# atsams70n-switch.net
KiCad netlist of a schematic drawn in EAGLE
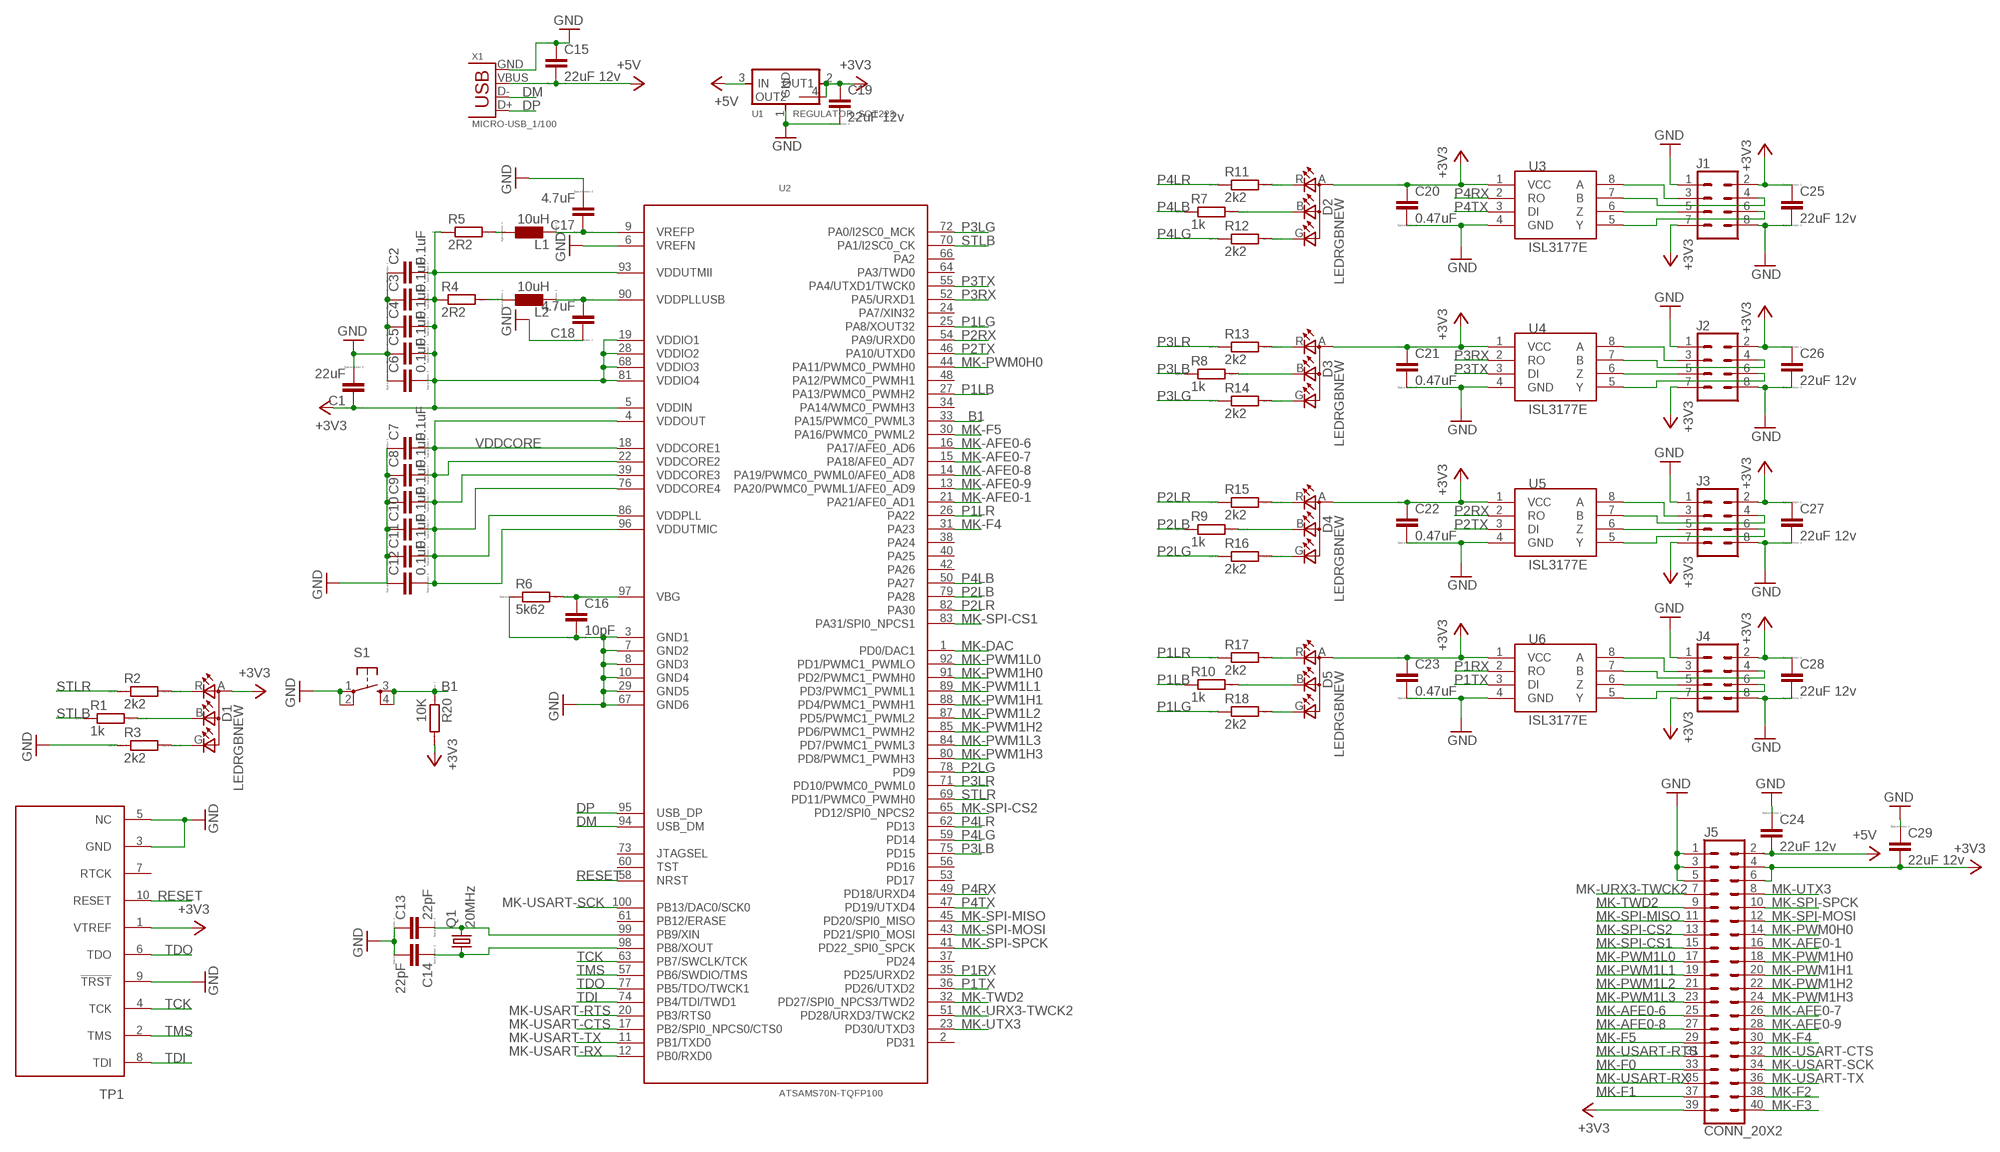
[diagram p0: schematic, sheet 1]

(export (version "E")
  (design (tool "Eeschema 10.0.6"))
  (components
    (comp (ref "C1")
      (value "22uF")
      (footprint "eagle-import:C0805")
      (libsource (lib "eagle-import") (part "C"))
    )
    (comp (ref "C2")
      (value "0.1uF")
      (footprint "eagle-import:C0603")
      (libsource (lib "eagle-import") (part "CC0603"))
    )
    (comp (ref "C3")
      (value "0.1uF")
      (footprint "eagle-import:C0603")
      (libsource (lib "eagle-import") (part "CC0603"))
    )
    (comp (ref "C4")
      (value "0.1uF")
      (footprint "eagle-import:C0603")
      (libsource (lib "eagle-import") (part "CC0603"))
    )
    (comp (ref "C5")
      (value "0.1uF")
      (footprint "eagle-import:C0603")
      (libsource (lib "eagle-import") (part "CC0603"))
    )
    (comp (ref "C6")
      (value "0.1uF")
      (footprint "eagle-import:C0603")
      (libsource (lib "eagle-import") (part "CC0603"))
    )
    (comp (ref "C7")
      (value "0.1uF")
      (footprint "eagle-import:C0603")
      (libsource (lib "eagle-import") (part "CC0603"))
    )
    (comp (ref "C8")
      (value "0.1uF")
      (footprint "eagle-import:C0603")
      (libsource (lib "eagle-import") (part "CC0603"))
    )
    (comp (ref "C9")
      (value "0.1uF")
      (footprint "eagle-import:C0603")
      (libsource (lib "eagle-import") (part "CC0603"))
    )
    (comp (ref "C10")
      (value "0.1uF")
      (footprint "eagle-import:C0603")
      (libsource (lib "eagle-import") (part "CC0603"))
    )
    (comp (ref "C11")
      (value "0.1uF")
      (footprint "eagle-import:C0603")
      (libsource (lib "eagle-import") (part "CC0603"))
    )
    (comp (ref "C12")
      (value "0.1uF")
      (footprint "eagle-import:C0603")
      (libsource (lib "eagle-import") (part "CC0603"))
    )
    (comp (ref "C13")
      (value "22pF")
      (footprint "eagle-import:C0603")
      (libsource (lib "eagle-import") (part "CC0603"))
    )
    (comp (ref "C14")
      (value "22pF")
      (footprint "eagle-import:C0603")
      (libsource (lib "eagle-import") (part "CC0603"))
    )
    (comp (ref "C15")
      (value "22uF 12v")
      (footprint "eagle-import:C0805")
      (libsource (lib "eagle-import") (part "C"))
    )
    (comp (ref "C16")
      (value "10pF")
      (footprint "eagle-import:C0805")
      (libsource (lib "eagle-import") (part "C"))
    )
    (comp (ref "C17")
      (value "4.7uF")
      (footprint "eagle-import:C0805")
      (libsource (lib "eagle-import") (part "C"))
    )
    (comp (ref "C18")
      (value "4.7uF")
      (footprint "eagle-import:C0805")
      (libsource (lib "eagle-import") (part "C"))
    )
    (comp (ref "C19")
      (value "22uF 12v")
      (footprint "eagle-import:C0805")
      (libsource (lib "eagle-import") (part "C"))
    )
    (comp (ref "C20")
      (value "0.47uF")
      (footprint "eagle-import:C0805")
      (libsource (lib "eagle-import") (part "C"))
    )
    (comp (ref "C21")
      (value "0.47uF")
      (footprint "eagle-import:C0805")
      (libsource (lib "eagle-import") (part "C"))
    )
    (comp (ref "C22")
      (value "0.47uF")
      (footprint "eagle-import:C0805")
      (libsource (lib "eagle-import") (part "C"))
    )
    (comp (ref "C23")
      (value "0.47uF")
      (footprint "eagle-import:C0805")
      (libsource (lib "eagle-import") (part "C"))
    )
    (comp (ref "C24")
      (value "22uF 12v")
      (footprint "eagle-import:C0805")
      (libsource (lib "eagle-import") (part "C"))
    )
    (comp (ref "C25")
      (value "22uF 12v")
      (footprint "eagle-import:C0805")
      (libsource (lib "eagle-import") (part "C"))
    )
    (comp (ref "C26")
      (value "22uF 12v")
      (footprint "eagle-import:C0805")
      (libsource (lib "eagle-import") (part "C"))
    )
    (comp (ref "C27")
      (value "22uF 12v")
      (footprint "eagle-import:C0805")
      (libsource (lib "eagle-import") (part "C"))
    )
    (comp (ref "C28")
      (value "22uF 12v")
      (footprint "eagle-import:C0805")
      (libsource (lib "eagle-import") (part "C"))
    )
    (comp (ref "C29")
      (value "22uF 12v")
      (footprint "eagle-import:C0805")
      (libsource (lib "eagle-import") (part "C"))
    )
    (comp (ref "D1")
      (value "LEDRGBNEW")
      (footprint "eagle-import:P-LCC-4")
      (libsource (lib "eagle-import") (part "LEDRGBNEW"))
    )
    (comp (ref "D2")
      (value "LEDRGBNEW")
      (footprint "eagle-import:P-LCC-4")
      (libsource (lib "eagle-import") (part "LEDRGBNEW"))
    )
    (comp (ref "D3")
      (value "LEDRGBNEW")
      (footprint "eagle-import:P-LCC-4")
      (libsource (lib "eagle-import") (part "LEDRGBNEW"))
    )
    (comp (ref "D4")
      (value "LEDRGBNEW")
      (footprint "eagle-import:P-LCC-4")
      (libsource (lib "eagle-import") (part "LEDRGBNEW"))
    )
    (comp (ref "D5")
      (value "LEDRGBNEW")
      (footprint "eagle-import:P-LCC-4")
      (libsource (lib "eagle-import") (part "LEDRGBNEW"))
    )
    (comp (ref "J1")
      (value "CONN_04X2SHROUDED")
      (footprint "eagle-import:2X4-SHROUDED")
      (libsource (lib "eagle-import") (part "CONN_04X2SHROUDED"))
    )
    (comp (ref "J2")
      (value "CONN_04X2SHROUDED")
      (footprint "eagle-import:2X4-SHROUDED")
      (libsource (lib "eagle-import") (part "CONN_04X2SHROUDED"))
    )
    (comp (ref "J3")
      (value "CONN_04X2SHROUDED")
      (footprint "eagle-import:2X4-SHROUDED")
      (libsource (lib "eagle-import") (part "CONN_04X2SHROUDED"))
    )
    (comp (ref "J4")
      (value "CONN_04X2SHROUDED")
      (footprint "eagle-import:2X4-SHROUDED")
      (libsource (lib "eagle-import") (part "CONN_04X2SHROUDED"))
    )
    (comp (ref "J5")
      (value "CONN_20X2")
      (footprint "eagle-import:2X20")
      (libsource (lib "eagle-import") (part "CONN_20X2"))
    )
    (comp (ref "L1")
      (value "10uH")
      (footprint "eagle-import:L1812")
      (libsource (lib "eagle-import") (part "L"))
    )
    (comp (ref "L2")
      (value "10uH")
      (footprint "eagle-import:L1812")
      (libsource (lib "eagle-import") (part "L"))
    )
    (comp (ref "Q1")
      (value "20MHz")
      (footprint "eagle-import:CTS406")
      (libsource (lib "eagle-import") (part "CRYSTALCTS406"))
    )
    (comp (ref "R1")
      (value "1k")
      (footprint "eagle-import:R0805")
      (libsource (lib "eagle-import") (part "R"))
    )
    (comp (ref "R2")
      (value "2k2")
      (footprint "eagle-import:R0805")
      (libsource (lib "eagle-import") (part "R"))
    )
    (comp (ref "R3")
      (value "2k2")
      (footprint "eagle-import:R0805")
      (libsource (lib "eagle-import") (part "R"))
    )
    (comp (ref "R4")
      (value "2R2")
      (footprint "eagle-import:R0805")
      (libsource (lib "eagle-import") (part "R"))
    )
    (comp (ref "R5")
      (value "2R2")
      (footprint "eagle-import:R0805")
      (libsource (lib "eagle-import") (part "R"))
    )
    (comp (ref "R6")
      (value "5k62")
      (footprint "eagle-import:R0805")
      (libsource (lib "eagle-import") (part "R"))
    )
    (comp (ref "R7")
      (value "1k")
      (footprint "eagle-import:R0805")
      (libsource (lib "eagle-import") (part "R"))
    )
    (comp (ref "R8")
      (value "1k")
      (footprint "eagle-import:R0805")
      (libsource (lib "eagle-import") (part "R"))
    )
    (comp (ref "R9")
      (value "1k")
      (footprint "eagle-import:R0805")
      (libsource (lib "eagle-import") (part "R"))
    )
    (comp (ref "R10")
      (value "1k")
      (footprint "eagle-import:R0805")
      (libsource (lib "eagle-import") (part "R"))
    )
    (comp (ref "R11")
      (value "2k2")
      (footprint "eagle-import:R0805")
      (libsource (lib "eagle-import") (part "R"))
    )
    (comp (ref "R12")
      (value "2k2")
      (footprint "eagle-import:R0805")
      (libsource (lib "eagle-import") (part "R"))
    )
    (comp (ref "R13")
      (value "2k2")
      (footprint "eagle-import:R0805")
      (libsource (lib "eagle-import") (part "R"))
    )
    (comp (ref "R14")
      (value "2k2")
      (footprint "eagle-import:R0805")
      (libsource (lib "eagle-import") (part "R"))
    )
    (comp (ref "R15")
      (value "2k2")
      (footprint "eagle-import:R0805")
      (libsource (lib "eagle-import") (part "R"))
    )
    (comp (ref "R16")
      (value "2k2")
      (footprint "eagle-import:R0805")
      (libsource (lib "eagle-import") (part "R"))
    )
    (comp (ref "R17")
      (value "2k2")
      (footprint "eagle-import:R0805")
      (libsource (lib "eagle-import") (part "R"))
    )
    (comp (ref "R18")
      (value "2k2")
      (footprint "eagle-import:R0805")
      (libsource (lib "eagle-import") (part "R"))
    )
    (comp (ref "R20")
      (value "10K")
      (footprint "eagle-import:R0805")
      (libsource (lib "eagle-import") (part "R"))
    )
    (comp (ref "S1")
      (value "6MM_SWITCH6MM_SWITCH")
      (footprint "eagle-import:6MM_SWITCH")
      (libsource (lib "eagle-import") (part "6MM_SWITCH6MM_SWITCH"))
    )
    (comp (ref "TP1")
      (value "TC2050-MCP-NL")
      (footprint "eagle-import:TC2030-MCP-NL")
      (libsource (lib "eagle-import") (part "TC2050-MCP-NL"))
    )
    (comp (ref "U1")
      (value "REGULATOR_SOT223")
      (footprint "eagle-import:SOT223")
      (libsource (lib "eagle-import") (part "REGULATOR_SOT223"))
    )
    (comp (ref "U2")
      (value "ATSAMS70N-TQFP100")
      (footprint "eagle-import:TQFP100-14X14")
      (libsource (lib "eagle-import") (part "ATSAMS70N-TQFP100"))
    )
    (comp (ref "U3")
      (value "ISL3177E")
      (footprint "eagle-import:MSOP8")
      (libsource (lib "eagle-import") (part "ISL3177E"))
    )
    (comp (ref "U4")
      (value "ISL3177E")
      (footprint "eagle-import:MSOP8")
      (libsource (lib "eagle-import") (part "ISL3177E"))
    )
    (comp (ref "U5")
      (value "ISL3177E")
      (footprint "eagle-import:MSOP8")
      (libsource (lib "eagle-import") (part "ISL3177E"))
    )
    (comp (ref "U6")
      (value "ISL3177E")
      (footprint "eagle-import:MSOP8")
      (libsource (lib "eagle-import") (part "ISL3177E"))
    )
    (comp (ref "X1")
      (value "MICRO-USB_1/100")
      (footprint "eagle-import:DX4R005HJ5_100")
      (libsource (lib "eagle-import") (part "MICRO-USB_1/100"))
    )
  )
  (nets
    (net (code "1") (name "+3V3") (class "Default")
      (node (ref "C1") (pin "1") (pinfunction "1_1") (pintype "passive"))
      (node (ref "C19") (pin "1") (pinfunction "1_1") (pintype "passive"))
      (node (ref "C2") (pin "2") (pinfunction "2_2") (pintype "passive"))
      (node (ref "C20") (pin "1") (pinfunction "1_1") (pintype "passive"))
      (node (ref "C21") (pin "1") (pinfunction "1_1") (pintype "passive"))
      (node (ref "C22") (pin "1") (pinfunction "1_1") (pintype "passive"))
      (node (ref "C23") (pin "1") (pinfunction "1_1") (pintype "passive"))
      (node (ref "C25") (pin "1") (pinfunction "1_1") (pintype "passive"))
      (node (ref "C26") (pin "1") (pinfunction "1_1") (pintype "passive"))
      (node (ref "C27") (pin "1") (pinfunction "1_1") (pintype "passive"))
      (node (ref "C28") (pin "1") (pinfunction "1_1") (pintype "passive"))
      (node (ref "C29") (pin "2") (pinfunction "2_2") (pintype "passive"))
      (node (ref "C3") (pin "2") (pinfunction "2_2") (pintype "passive"))
      (node (ref "C4") (pin "2") (pinfunction "2_2") (pintype "passive"))
      (node (ref "C5") (pin "2") (pinfunction "2_2") (pintype "passive"))
      (node (ref "C6") (pin "2") (pinfunction "2_2") (pintype "passive"))
      (node (ref "D1") (pin "A") (pinfunction "A2_A") (pintype "passive"))
      (node (ref "D2") (pin "A") (pinfunction "A2_A") (pintype "passive"))
      (node (ref "D3") (pin "A") (pinfunction "A2_A") (pintype "passive"))
      (node (ref "D4") (pin "A") (pinfunction "A2_A") (pintype "passive"))
      (node (ref "D5") (pin "A") (pinfunction "A2_A") (pintype "passive"))
      (node (ref "J1") (pin "2") (pinfunction "2_2") (pintype "passive"))
      (node (ref "J1") (pin "7") (pinfunction "7_7") (pintype "passive"))
      (node (ref "J2") (pin "2") (pinfunction "2_2") (pintype "passive"))
      (node (ref "J2") (pin "7") (pinfunction "7_7") (pintype "passive"))
      (node (ref "J3") (pin "2") (pinfunction "2_2") (pintype "passive"))
      (node (ref "J3") (pin "7") (pinfunction "7_7") (pintype "passive"))
      (node (ref "J4") (pin "2") (pinfunction "2_2") (pintype "passive"))
      (node (ref "J4") (pin "7") (pinfunction "7_7") (pintype "passive"))
      (node (ref "J5") (pin "39") (pinfunction "39_39") (pintype "passive"))
      (node (ref "J5") (pin "4") (pinfunction "4_4") (pintype "passive"))
      (node (ref "J5") (pin "6") (pinfunction "6_6") (pintype "passive"))
      (node (ref "R20") (pin "2") (pinfunction "2_2") (pintype "passive"))
      (node (ref "R4") (pin "1") (pinfunction "1_1") (pintype "passive"))
      (node (ref "R5") (pin "1") (pinfunction "1_1") (pintype "passive"))
      (node (ref "TP1") (pin "1") (pinfunction "VTREF_1") (pintype "bidirectional"))
      (node (ref "U1") (pin "2") (pinfunction "OUT1_2") (pintype "bidirectional"))
      (node (ref "U1") (pin "4") (pinfunction "OUT2_4") (pintype "bidirectional"))
      (node (ref "U2") (pin "19") (pinfunction "VDDIO1_19") (pintype "bidirectional"))
      (node (ref "U2") (pin "28") (pinfunction "VDDIO2_28") (pintype "bidirectional"))
      (node (ref "U2") (pin "5") (pinfunction "VDDIN_5") (pintype "bidirectional"))
      (node (ref "U2") (pin "68") (pinfunction "VDDIO3_68") (pintype "bidirectional"))
      (node (ref "U2") (pin "81") (pinfunction "VDDIO4_81") (pintype "bidirectional"))
      (node (ref "U2") (pin "93") (pinfunction "VDDUTMII_93") (pintype "bidirectional"))
      (node (ref "U3") (pin "1") (pinfunction "VCC_1") (pintype "bidirectional"))
      (node (ref "U4") (pin "1") (pinfunction "VCC_1") (pintype "bidirectional"))
      (node (ref "U5") (pin "1") (pinfunction "VCC_1") (pintype "bidirectional"))
      (node (ref "U6") (pin "1") (pinfunction "VCC_1") (pintype "bidirectional"))
    )
    (net (code "2") (name "+5V") (class "Default")
      (node (ref "C15") (pin "2") (pinfunction "2_2") (pintype "passive"))
      (node (ref "C24") (pin "2") (pinfunction "2_2") (pintype "passive"))
      (node (ref "J5") (pin "2") (pinfunction "2_2") (pintype "passive"))
      (node (ref "U1") (pin "3") (pinfunction "IN_3") (pintype "bidirectional"))
      (node (ref "X1") (pin "VBUS") (pinfunction "VBUS_VBUS") (pintype "bidirectional"))
    )
    (net (code "3") (name "/B1") (class "Default")
      (node (ref "R20") (pin "1") (pinfunction "1_1") (pintype "passive"))
      (node (ref "S1") (pin "3") (pinfunction "S_3") (pintype "passive"))
      (node (ref "S1") (pin "4") (pinfunction "S1_4") (pintype "passive"))
      (node (ref "U2") (pin "33") (pinfunction "PA15/PWMC0_PWML3_33") (pintype "bidirectional"))
    )
    (net (code "4") (name "/DM") (class "Default")
      (node (ref "U2") (pin "94") (pinfunction "USB_DM_94") (pintype "bidirectional"))
      (node (ref "X1") (pin "D-") (pinfunction "D-_D-") (pintype "bidirectional"))
    )
    (net (code "5") (name "/DP") (class "Default")
      (node (ref "U2") (pin "95") (pinfunction "USB_DP_95") (pintype "bidirectional"))
      (node (ref "X1") (pin "D+") (pinfunction "D+_D+") (pintype "bidirectional"))
    )
    (net (code "6") (name "/MK-AFE0-1") (class "Default")
      (node (ref "J5") (pin "16") (pinfunction "16_16") (pintype "passive"))
      (node (ref "U2") (pin "21") (pinfunction "PA21/AFE0_AD1_21") (pintype "bidirectional"))
    )
    (net (code "7") (name "/MK-AFE0-6") (class "Default")
      (node (ref "J5") (pin "25") (pinfunction "25_25") (pintype "passive"))
      (node (ref "U2") (pin "16") (pinfunction "PA17/AFE0_AD6_16") (pintype "bidirectional"))
    )
    (net (code "8") (name "/MK-AFE0-7") (class "Default")
      (node (ref "J5") (pin "26") (pinfunction "26_26") (pintype "passive"))
      (node (ref "U2") (pin "15") (pinfunction "PA18/AFE0_AD7_15") (pintype "bidirectional"))
    )
    (net (code "9") (name "/MK-AFE0-8") (class "Default")
      (node (ref "J5") (pin "27") (pinfunction "27_27") (pintype "passive"))
      (node (ref "U2") (pin "14") (pinfunction "PA19/PWMC0_PWML0/AFE0_AD8_14") (pintype "bidirectional"))
    )
    (net (code "10") (name "/MK-AFE0-9") (class "Default")
      (node (ref "J5") (pin "28") (pinfunction "28_28") (pintype "passive"))
      (node (ref "U2") (pin "13") (pinfunction "PA20/PWMC0_PWML1/AFE0_AD9_13") (pintype "bidirectional"))
    )
    (net (code "11") (name "/MK-DAC") (class "Default")
      (node (ref "U2") (pin "1") (pinfunction "PD0/DAC1_1") (pintype "bidirectional"))
    )
    (net (code "12") (name "/MK-F0") (class "Default")
      (node (ref "J5") (pin "33") (pinfunction "33_33") (pintype "passive"))
    )
    (net (code "13") (name "/MK-F1") (class "Default")
      (node (ref "J5") (pin "37") (pinfunction "37_37") (pintype "passive"))
    )
    (net (code "14") (name "/MK-F2") (class "Default")
      (node (ref "J5") (pin "38") (pinfunction "38_38") (pintype "passive"))
    )
    (net (code "15") (name "/MK-F3") (class "Default")
      (node (ref "J5") (pin "40") (pinfunction "40_40") (pintype "passive"))
    )
    (net (code "16") (name "/MK-F4") (class "Default")
      (node (ref "J5") (pin "30") (pinfunction "30_30") (pintype "passive"))
      (node (ref "U2") (pin "31") (pinfunction "PA23_31") (pintype "bidirectional"))
    )
    (net (code "17") (name "/MK-F5") (class "Default")
      (node (ref "J5") (pin "29") (pinfunction "29_29") (pintype "passive"))
      (node (ref "U2") (pin "30") (pinfunction "PA16/PWMC0_PWML2_30") (pintype "bidirectional"))
    )
    (net (code "18") (name "/MK-PWM0H0") (class "Default")
      (node (ref "J5") (pin "14") (pinfunction "14_14") (pintype "passive"))
      (node (ref "U2") (pin "44") (pinfunction "PA11/PWMC0_PWMH0_44") (pintype "bidirectional"))
    )
    (net (code "19") (name "/MK-PWM1H0") (class "Default")
      (node (ref "J5") (pin "18") (pinfunction "18_18") (pintype "passive"))
      (node (ref "U2") (pin "91") (pinfunction "PD2/PWMC1_PWMH0_91") (pintype "bidirectional"))
    )
    (net (code "20") (name "/MK-PWM1H1") (class "Default")
      (node (ref "J5") (pin "20") (pinfunction "20_20") (pintype "passive"))
      (node (ref "U2") (pin "88") (pinfunction "PD4/PWMC1_PWMH1_88") (pintype "bidirectional"))
    )
    (net (code "21") (name "/MK-PWM1H2") (class "Default")
      (node (ref "J5") (pin "22") (pinfunction "22_22") (pintype "passive"))
      (node (ref "U2") (pin "85") (pinfunction "PD6/PWMC1_PWMH2_85") (pintype "bidirectional"))
    )
    (net (code "22") (name "/MK-PWM1H3") (class "Default")
      (node (ref "J5") (pin "24") (pinfunction "24_24") (pintype "passive"))
      (node (ref "U2") (pin "80") (pinfunction "PD8/PWMC1_PWMH3_80") (pintype "bidirectional"))
    )
    (net (code "23") (name "/MK-PWM1L0") (class "Default")
      (node (ref "J5") (pin "17") (pinfunction "17_17") (pintype "passive"))
      (node (ref "U2") (pin "92") (pinfunction "PD1/PWMC1_PWMLO_92") (pintype "bidirectional"))
    )
    (net (code "24") (name "/MK-PWM1L1") (class "Default")
      (node (ref "J5") (pin "19") (pinfunction "19_19") (pintype "passive"))
      (node (ref "U2") (pin "89") (pinfunction "PD3/PWMC1_PWML1_89") (pintype "bidirectional"))
    )
    (net (code "25") (name "/MK-PWM1L2") (class "Default")
      (node (ref "J5") (pin "21") (pinfunction "21_21") (pintype "passive"))
      (node (ref "U2") (pin "87") (pinfunction "PD5/PWMC1_PWML2_87") (pintype "bidirectional"))
    )
    (net (code "26") (name "/MK-PWM1L3") (class "Default")
      (node (ref "J5") (pin "23") (pinfunction "23_23") (pintype "passive"))
      (node (ref "U2") (pin "84") (pinfunction "PD7/PWMC1_PWML3_84") (pintype "bidirectional"))
    )
    (net (code "27") (name "/MK-SPI-CS1") (class "Default")
      (node (ref "J5") (pin "15") (pinfunction "15_15") (pintype "passive"))
      (node (ref "U2") (pin "83") (pinfunction "PA31/SPI0_NPCS1_83") (pintype "bidirectional"))
    )
    (net (code "28") (name "/MK-SPI-CS2") (class "Default")
      (node (ref "J5") (pin "13") (pinfunction "13_13") (pintype "passive"))
      (node (ref "U2") (pin "65") (pinfunction "PD12/SPI0_NPCS2_65") (pintype "bidirectional"))
    )
    (net (code "29") (name "/MK-SPI-MISO") (class "Default")
      (node (ref "J5") (pin "11") (pinfunction "11_11") (pintype "passive"))
      (node (ref "U2") (pin "45") (pinfunction "PD20/SPI0_MISO_45") (pintype "bidirectional"))
    )
    (net (code "30") (name "/MK-SPI-MOSI") (class "Default")
      (node (ref "J5") (pin "12") (pinfunction "12_12") (pintype "passive"))
      (node (ref "U2") (pin "43") (pinfunction "PD21/SPI0_MOSI_43") (pintype "bidirectional"))
    )
    (net (code "31") (name "/MK-SPI-SPCK") (class "Default")
      (node (ref "J5") (pin "10") (pinfunction "10_10") (pintype "passive"))
      (node (ref "U2") (pin "41") (pinfunction "PD22_SPI0_SPCK_41") (pintype "bidirectional"))
    )
    (net (code "32") (name "/MK-TWD2") (class "Default")
      (node (ref "J5") (pin "9") (pinfunction "9_9") (pintype "passive"))
      (node (ref "U2") (pin "32") (pinfunction "PD27/SPI0_NPCS3/TWD2_32") (pintype "bidirectional"))
    )
    (net (code "33") (name "/MK-URX3-TWCK2") (class "Default")
      (node (ref "J5") (pin "7") (pinfunction "7_7") (pintype "passive"))
      (node (ref "U2") (pin "51") (pinfunction "PD28/URXD3/TWCK2_51") (pintype "bidirectional"))
    )
    (net (code "34") (name "/MK-USART-CTS") (class "Default")
      (node (ref "J5") (pin "32") (pinfunction "32_32") (pintype "passive"))
      (node (ref "U2") (pin "17") (pinfunction "PB2/SPI0_NPCS0/CTS0_17") (pintype "bidirectional"))
    )
    (net (code "35") (name "/MK-USART-RTS") (class "Default")
      (node (ref "J5") (pin "31") (pinfunction "31_31") (pintype "passive"))
      (node (ref "U2") (pin "20") (pinfunction "PB3/RTS0_20") (pintype "bidirectional"))
    )
    (net (code "36") (name "/MK-USART-RX") (class "Default")
      (node (ref "J5") (pin "35") (pinfunction "35_35") (pintype "passive"))
      (node (ref "U2") (pin "12") (pinfunction "PB0/RXD0_12") (pintype "bidirectional"))
    )
    (net (code "37") (name "/MK-USART-SCK") (class "Default")
      (node (ref "J5") (pin "34") (pinfunction "34_34") (pintype "passive"))
      (node (ref "U2") (pin "100") (pinfunction "PB13/DAC0/SCK0_100") (pintype "bidirectional"))
    )
    (net (code "38") (name "/MK-USART-TX") (class "Default")
      (node (ref "J5") (pin "36") (pinfunction "36_36") (pintype "passive"))
      (node (ref "U2") (pin "11") (pinfunction "PB1/TXD0_11") (pintype "bidirectional"))
    )
    (net (code "39") (name "/MK-UTX3") (class "Default")
      (node (ref "J5") (pin "8") (pinfunction "8_8") (pintype "passive"))
      (node (ref "U2") (pin "23") (pinfunction "PD30/UTXD3_23") (pintype "bidirectional"))
    )
    (net (code "40") (name "/P1LB") (class "Default")
      (node (ref "R10") (pin "1") (pinfunction "1_1") (pintype "passive"))
      (node (ref "U2") (pin "27") (pinfunction "PA13/PWMC0_PWMH2_27") (pintype "bidirectional"))
    )
    (net (code "41") (name "/P1LG") (class "Default")
      (node (ref "R18") (pin "1") (pinfunction "1_1") (pintype "passive"))
      (node (ref "U2") (pin "25") (pinfunction "PA8/XOUT32_25") (pintype "bidirectional"))
    )
    (net (code "42") (name "/P1LR") (class "Default")
      (node (ref "R17") (pin "1") (pinfunction "1_1") (pintype "passive"))
      (node (ref "U2") (pin "26") (pinfunction "PA22_26") (pintype "bidirectional"))
    )
    (net (code "43") (name "/P1RX") (class "Default")
      (node (ref "U2") (pin "35") (pinfunction "PD25/URXD2_35") (pintype "bidirectional"))
      (node (ref "U6") (pin "2") (pinfunction "RO_2") (pintype "bidirectional"))
    )
    (net (code "44") (name "/P1TX") (class "Default")
      (node (ref "U2") (pin "36") (pinfunction "PD26/UTXD2_36") (pintype "bidirectional"))
      (node (ref "U6") (pin "3") (pinfunction "DI_3") (pintype "bidirectional"))
    )
    (net (code "45") (name "/P2LB") (class "Default")
      (node (ref "R9") (pin "1") (pinfunction "1_1") (pintype "passive"))
      (node (ref "U2") (pin "79") (pinfunction "PA28_79") (pintype "bidirectional"))
    )
    (net (code "46") (name "/P2LG") (class "Default")
      (node (ref "R16") (pin "1") (pinfunction "1_1") (pintype "passive"))
      (node (ref "U2") (pin "78") (pinfunction "PD9_78") (pintype "bidirectional"))
    )
    (net (code "47") (name "/P2LR") (class "Default")
      (node (ref "R15") (pin "1") (pinfunction "1_1") (pintype "passive"))
      (node (ref "U2") (pin "82") (pinfunction "PA30_82") (pintype "bidirectional"))
    )
    (net (code "48") (name "/P2RX") (class "Default")
      (node (ref "U2") (pin "54") (pinfunction "PA9/URXD0_54") (pintype "bidirectional"))
      (node (ref "U5") (pin "2") (pinfunction "RO_2") (pintype "bidirectional"))
    )
    (net (code "49") (name "/P2TX") (class "Default")
      (node (ref "U2") (pin "46") (pinfunction "PA10/UTXD0_46") (pintype "bidirectional"))
      (node (ref "U5") (pin "3") (pinfunction "DI_3") (pintype "bidirectional"))
    )
    (net (code "50") (name "/P3LB") (class "Default")
      (node (ref "R8") (pin "1") (pinfunction "1_1") (pintype "passive"))
      (node (ref "U2") (pin "75") (pinfunction "PD15_75") (pintype "bidirectional"))
    )
    (net (code "51") (name "/P3LG") (class "Default")
      (node (ref "R14") (pin "1") (pinfunction "1_1") (pintype "passive"))
      (node (ref "U2") (pin "72") (pinfunction "PA0/I2SC0_MCK_72") (pintype "bidirectional"))
    )
    (net (code "52") (name "/P3LR") (class "Default")
      (node (ref "R13") (pin "1") (pinfunction "1_1") (pintype "passive"))
      (node (ref "U2") (pin "71") (pinfunction "PD10/PWMC0_PWML0_71") (pintype "bidirectional"))
    )
    (net (code "53") (name "/P3RX") (class "Default")
      (node (ref "U2") (pin "52") (pinfunction "PA5/URXD1_52") (pintype "bidirectional"))
      (node (ref "U4") (pin "2") (pinfunction "RO_2") (pintype "bidirectional"))
    )
    (net (code "54") (name "/P3TX") (class "Default")
      (node (ref "U2") (pin "55") (pinfunction "PA4/UTXD1/TWCK0_55") (pintype "bidirectional"))
      (node (ref "U4") (pin "3") (pinfunction "DI_3") (pintype "bidirectional"))
    )
    (net (code "55") (name "/P4LB") (class "Default")
      (node (ref "R7") (pin "1") (pinfunction "1_1") (pintype "passive"))
      (node (ref "U2") (pin "50") (pinfunction "PA27_50") (pintype "bidirectional"))
    )
    (net (code "56") (name "/P4LG") (class "Default")
      (node (ref "R12") (pin "1") (pinfunction "1_1") (pintype "passive"))
      (node (ref "U2") (pin "59") (pinfunction "PD14_59") (pintype "bidirectional"))
    )
    (net (code "57") (name "/P4LR") (class "Default")
      (node (ref "R11") (pin "1") (pinfunction "1_1") (pintype "passive"))
      (node (ref "U2") (pin "62") (pinfunction "PD13_62") (pintype "bidirectional"))
    )
    (net (code "58") (name "/P4RX") (class "Default")
      (node (ref "U2") (pin "49") (pinfunction "PD18/URXD4_49") (pintype "bidirectional"))
      (node (ref "U3") (pin "2") (pinfunction "RO_2") (pintype "bidirectional"))
    )
    (net (code "59") (name "/P4TX") (class "Default")
      (node (ref "U2") (pin "47") (pinfunction "PD19/UTXD4_47") (pintype "bidirectional"))
      (node (ref "U3") (pin "3") (pinfunction "DI_3") (pintype "bidirectional"))
    )
    (net (code "60") (name "/RESET") (class "Default")
      (node (ref "TP1") (pin "10") (pinfunction "RESET_10") (pintype "bidirectional"))
      (node (ref "U2") (pin "58") (pinfunction "NRST_58") (pintype "bidirectional"))
    )
    (net (code "61") (name "/STLB") (class "Default")
      (node (ref "R1") (pin "1") (pinfunction "1_1") (pintype "passive"))
      (node (ref "U2") (pin "70") (pinfunction "PA1/I2SC0_CK_70") (pintype "bidirectional"))
    )
    (net (code "62") (name "/STLR") (class "Default")
      (node (ref "R2") (pin "1") (pinfunction "1_1") (pintype "passive"))
      (node (ref "U2") (pin "69") (pinfunction "PD11/PWMC0_PWMH0_69") (pintype "bidirectional"))
    )
    (net (code "63") (name "/TCK") (class "Default")
      (node (ref "TP1") (pin "4") (pinfunction "TCK_4") (pintype "bidirectional"))
      (node (ref "U2") (pin "63") (pinfunction "PB7/SWCLK/TCK_63") (pintype "bidirectional"))
    )
    (net (code "64") (name "/TDI") (class "Default")
      (node (ref "TP1") (pin "8") (pinfunction "TDI_8") (pintype "bidirectional"))
      (node (ref "U2") (pin "74") (pinfunction "PB4/TDI/TWD1_74") (pintype "bidirectional"))
    )
    (net (code "65") (name "/TDO") (class "Default")
      (node (ref "TP1") (pin "6") (pinfunction "TDO_6") (pintype "bidirectional"))
      (node (ref "U2") (pin "77") (pinfunction "PB5/TDO/TWCK1_77") (pintype "bidirectional"))
    )
    (net (code "66") (name "/TMS") (class "Default")
      (node (ref "TP1") (pin "2") (pinfunction "TMS_2") (pintype "bidirectional"))
      (node (ref "U2") (pin "57") (pinfunction "PB6/SWDIO/TMS_57") (pintype "bidirectional"))
    )
    (net (code "67") (name "/VDDCORE") (class "Default")
      (node (ref "C10") (pin "2") (pinfunction "2_2") (pintype "passive"))
      (node (ref "C11") (pin "2") (pinfunction "2_2") (pintype "passive"))
      (node (ref "C12") (pin "2") (pinfunction "2_2") (pintype "passive"))
      (node (ref "C7") (pin "2") (pinfunction "2_2") (pintype "passive"))
      (node (ref "C8") (pin "2") (pinfunction "2_2") (pintype "passive"))
      (node (ref "C9") (pin "2") (pinfunction "2_2") (pintype "passive"))
      (node (ref "U2") (pin "18") (pinfunction "VDDCORE1_18") (pintype "bidirectional"))
      (node (ref "U2") (pin "22") (pinfunction "VDDCORE2_22") (pintype "bidirectional"))
      (node (ref "U2") (pin "39") (pinfunction "VDDCORE3_39") (pintype "bidirectional"))
      (node (ref "U2") (pin "4") (pinfunction "VDDOUT_4") (pintype "bidirectional"))
      (node (ref "U2") (pin "76") (pinfunction "VDDCORE4_76") (pintype "bidirectional"))
      (node (ref "U2") (pin "86") (pinfunction "VDDPLL_86") (pintype "bidirectional"))
      (node (ref "U2") (pin "96") (pinfunction "VDDUTMIC_96") (pintype "bidirectional"))
    )
    (net (code "68") (name "GND") (class "Default")
      (node (ref "C1") (pin "2") (pinfunction "2_2") (pintype "passive"))
      (node (ref "C10") (pin "1") (pinfunction "1_1") (pintype "passive"))
      (node (ref "C11") (pin "1") (pinfunction "1_1") (pintype "passive"))
      (node (ref "C12") (pin "1") (pinfunction "1_1") (pintype "passive"))
      (node (ref "C13") (pin "1") (pinfunction "1_1") (pintype "passive"))
      (node (ref "C14") (pin "2") (pinfunction "2_2") (pintype "passive"))
      (node (ref "C15") (pin "1") (pinfunction "1_1") (pintype "passive"))
      (node (ref "C16") (pin "2") (pinfunction "2_2") (pintype "passive"))
      (node (ref "C17") (pin "2") (pinfunction "2_2") (pintype "passive"))
      (node (ref "C18") (pin "1") (pinfunction "1_1") (pintype "passive"))
      (node (ref "C19") (pin "2") (pinfunction "2_2") (pintype "passive"))
      (node (ref "C2") (pin "1") (pinfunction "1_1") (pintype "passive"))
      (node (ref "C20") (pin "2") (pinfunction "2_2") (pintype "passive"))
      (node (ref "C21") (pin "2") (pinfunction "2_2") (pintype "passive"))
      (node (ref "C22") (pin "2") (pinfunction "2_2") (pintype "passive"))
      (node (ref "C23") (pin "2") (pinfunction "2_2") (pintype "passive"))
      (node (ref "C24") (pin "1") (pinfunction "1_1") (pintype "passive"))
      (node (ref "C25") (pin "2") (pinfunction "2_2") (pintype "passive"))
      (node (ref "C26") (pin "2") (pinfunction "2_2") (pintype "passive"))
      (node (ref "C27") (pin "2") (pinfunction "2_2") (pintype "passive"))
      (node (ref "C28") (pin "2") (pinfunction "2_2") (pintype "passive"))
      (node (ref "C29") (pin "1") (pinfunction "1_1") (pintype "passive"))
      (node (ref "C3") (pin "1") (pinfunction "1_1") (pintype "passive"))
      (node (ref "C4") (pin "1") (pinfunction "1_1") (pintype "passive"))
      (node (ref "C5") (pin "1") (pinfunction "1_1") (pintype "passive"))
      (node (ref "C6") (pin "1") (pinfunction "1_1") (pintype "passive"))
      (node (ref "C7") (pin "1") (pinfunction "1_1") (pintype "passive"))
      (node (ref "C8") (pin "1") (pinfunction "1_1") (pintype "passive"))
      (node (ref "C9") (pin "1") (pinfunction "1_1") (pintype "passive"))
      (node (ref "J1") (pin "1") (pinfunction "1_1") (pintype "passive"))
      (node (ref "J1") (pin "8") (pinfunction "8_8") (pintype "passive"))
      (node (ref "J2") (pin "1") (pinfunction "1_1") (pintype "passive"))
      (node (ref "J2") (pin "8") (pinfunction "8_8") (pintype "passive"))
      (node (ref "J3") (pin "1") (pinfunction "1_1") (pintype "passive"))
      (node (ref "J3") (pin "8") (pinfunction "8_8") (pintype "passive"))
      (node (ref "J4") (pin "1") (pinfunction "1_1") (pintype "passive"))
      (node (ref "J4") (pin "8") (pinfunction "8_8") (pintype "passive"))
      (node (ref "J5") (pin "1") (pinfunction "1_1") (pintype "passive"))
      (node (ref "J5") (pin "3") (pinfunction "3_3") (pintype "passive"))
      (node (ref "J5") (pin "5") (pinfunction "5_5") (pintype "passive"))
      (node (ref "R3") (pin "1") (pinfunction "1_1") (pintype "passive"))
      (node (ref "R6") (pin "1") (pinfunction "1_1") (pintype "passive"))
      (node (ref "S1") (pin "1") (pinfunction "P_1") (pintype "passive"))
      (node (ref "S1") (pin "2") (pinfunction "P1_2") (pintype "passive"))
      (node (ref "TP1") (pin "3") (pinfunction "GND_3") (pintype "bidirectional"))
      (node (ref "TP1") (pin "5") (pinfunction "NC_5") (pintype "bidirectional"))
      (node (ref "TP1") (pin "9") (pinfunction "~{TRST}_9") (pintype "bidirectional"))
      (node (ref "U1") (pin "1") (pinfunction "GND_1") (pintype "bidirectional"))
      (node (ref "U2") (pin "10") (pinfunction "GND4_10") (pintype "bidirectional"))
      (node (ref "U2") (pin "29") (pinfunction "GND5_29") (pintype "bidirectional"))
      (node (ref "U2") (pin "3") (pinfunction "GND1_3") (pintype "bidirectional"))
      (node (ref "U2") (pin "6") (pinfunction "VREFN_6") (pintype "bidirectional"))
      (node (ref "U2") (pin "67") (pinfunction "GND6_67") (pintype "bidirectional"))
      (node (ref "U2") (pin "7") (pinfunction "GND2_7") (pintype "bidirectional"))
      (node (ref "U2") (pin "8") (pinfunction "GND3_8") (pintype "bidirectional"))
      (node (ref "U3") (pin "4") (pinfunction "GND_4") (pintype "bidirectional"))
      (node (ref "U4") (pin "4") (pinfunction "GND_4") (pintype "bidirectional"))
      (node (ref "U5") (pin "4") (pinfunction "GND_4") (pintype "bidirectional"))
      (node (ref "U6") (pin "4") (pinfunction "GND_4") (pintype "bidirectional"))
      (node (ref "X1") (pin "GND") (pinfunction "GND_GND") (pintype "bidirectional"))
    )
    (net (code "69") (name "Net-(D1-CBLUE)") (class "Default")
      (node (ref "D1") (pin "B") (pinfunction "CBLUE_B") (pintype "passive"))
      (node (ref "R1") (pin "2") (pinfunction "2_2") (pintype "passive"))
    )
    (net (code "70") (name "Net-(D1-CGREEN)") (class "Default")
      (node (ref "D1") (pin "G") (pinfunction "CGREEN_G") (pintype "passive"))
      (node (ref "R3") (pin "2") (pinfunction "2_2") (pintype "passive"))
    )
    (net (code "71") (name "Net-(D1-CRED)") (class "Default")
      (node (ref "D1") (pin "R") (pinfunction "CRED_R") (pintype "passive"))
      (node (ref "R2") (pin "2") (pinfunction "2_2") (pintype "passive"))
    )
    (net (code "72") (name "Net-(D2-CBLUE)") (class "Default")
      (node (ref "D2") (pin "B") (pinfunction "CBLUE_B") (pintype "passive"))
      (node (ref "R7") (pin "2") (pinfunction "2_2") (pintype "passive"))
    )
    (net (code "73") (name "Net-(D2-CGREEN)") (class "Default")
      (node (ref "D2") (pin "G") (pinfunction "CGREEN_G") (pintype "passive"))
      (node (ref "R12") (pin "2") (pinfunction "2_2") (pintype "passive"))
    )
    (net (code "74") (name "Net-(D2-CRED)") (class "Default")
      (node (ref "D2") (pin "R") (pinfunction "CRED_R") (pintype "passive"))
      (node (ref "R11") (pin "2") (pinfunction "2_2") (pintype "passive"))
    )
    (net (code "75") (name "Net-(D3-CBLUE)") (class "Default")
      (node (ref "D3") (pin "B") (pinfunction "CBLUE_B") (pintype "passive"))
      (node (ref "R8") (pin "2") (pinfunction "2_2") (pintype "passive"))
    )
    (net (code "76") (name "Net-(D3-CGREEN)") (class "Default")
      (node (ref "D3") (pin "G") (pinfunction "CGREEN_G") (pintype "passive"))
      (node (ref "R14") (pin "2") (pinfunction "2_2") (pintype "passive"))
    )
    (net (code "77") (name "Net-(D3-CRED)") (class "Default")
      (node (ref "D3") (pin "R") (pinfunction "CRED_R") (pintype "passive"))
      (node (ref "R13") (pin "2") (pinfunction "2_2") (pintype "passive"))
    )
    (net (code "78") (name "Net-(D4-CBLUE)") (class "Default")
      (node (ref "D4") (pin "B") (pinfunction "CBLUE_B") (pintype "passive"))
      (node (ref "R9") (pin "2") (pinfunction "2_2") (pintype "passive"))
    )
    (net (code "79") (name "Net-(D4-CGREEN)") (class "Default")
      (node (ref "D4") (pin "G") (pinfunction "CGREEN_G") (pintype "passive"))
      (node (ref "R16") (pin "2") (pinfunction "2_2") (pintype "passive"))
    )
    (net (code "80") (name "Net-(D4-CRED)") (class "Default")
      (node (ref "D4") (pin "R") (pinfunction "CRED_R") (pintype "passive"))
      (node (ref "R15") (pin "2") (pinfunction "2_2") (pintype "passive"))
    )
    (net (code "81") (name "Net-(D5-CBLUE)") (class "Default")
      (node (ref "D5") (pin "B") (pinfunction "CBLUE_B") (pintype "passive"))
      (node (ref "R10") (pin "2") (pinfunction "2_2") (pintype "passive"))
    )
    (net (code "82") (name "Net-(D5-CGREEN)") (class "Default")
      (node (ref "D5") (pin "G") (pinfunction "CGREEN_G") (pintype "passive"))
      (node (ref "R18") (pin "2") (pinfunction "2_2") (pintype "passive"))
    )
    (net (code "83") (name "Net-(D5-CRED)") (class "Default")
      (node (ref "D5") (pin "R") (pinfunction "CRED_R") (pintype "passive"))
      (node (ref "R17") (pin "2") (pinfunction "2_2") (pintype "passive"))
    )
    (net (code "84") (name "Net-(L1-Pad1)") (class "Default")
      (node (ref "L1") (pin "1") (pinfunction "1_1") (pintype "passive"))
      (node (ref "R5") (pin "2") (pinfunction "2_2") (pintype "passive"))
    )
    (net (code "85") (name "Net-(L2-Pad1)") (class "Default")
      (node (ref "L2") (pin "1") (pinfunction "1_1") (pintype "passive"))
      (node (ref "R4") (pin "2") (pinfunction "2_2") (pintype "passive"))
    )
    (net (code "86") (name "Net-(Q1-2)") (class "Default")
      (node (ref "C13") (pin "2") (pinfunction "2_2") (pintype "passive"))
      (node (ref "Q1") (pin "3") (pinfunction "2_3") (pintype "passive"))
      (node (ref "U2") (pin "99") (pinfunction "PB9/XIN_99") (pintype "bidirectional"))
    )
    (net (code "87") (name "Net-(U2-PB8{slash}XOUT)") (class "Default")
      (node (ref "C14") (pin "1") (pinfunction "1_1") (pintype "passive"))
      (node (ref "Q1") (pin "1") (pinfunction "1_1") (pintype "passive"))
      (node (ref "U2") (pin "98") (pinfunction "PB8/XOUT_98") (pintype "bidirectional"))
    )
    (net (code "88") (name "Net-(U2-VBG)") (class "Default")
      (node (ref "C16") (pin "1") (pinfunction "1_1") (pintype "passive"))
      (node (ref "R6") (pin "2") (pinfunction "2_2") (pintype "passive"))
      (node (ref "U2") (pin "97") (pinfunction "VBG_97") (pintype "bidirectional"))
    )
    (net (code "89") (name "Net-(U2-VDDPLLUSB)") (class "Default")
      (node (ref "C18") (pin "2") (pinfunction "2_2") (pintype "passive"))
      (node (ref "L2") (pin "2") (pinfunction "2_2") (pintype "passive"))
      (node (ref "U2") (pin "90") (pinfunction "VDDPLLUSB_90") (pintype "bidirectional"))
    )
    (net (code "90") (name "Net-(U2-VREFP)") (class "Default")
      (node (ref "C17") (pin "1") (pinfunction "1_1") (pintype "passive"))
      (node (ref "L1") (pin "2") (pinfunction "2_2") (pintype "passive"))
      (node (ref "U2") (pin "9") (pinfunction "VREFP_9") (pintype "bidirectional"))
    )
    (net (code "91") (name "Net-(U3-A)") (class "Default")
      (node (ref "J1") (pin "3") (pinfunction "3_3") (pintype "passive"))
      (node (ref "U3") (pin "8") (pinfunction "A_8") (pintype "bidirectional"))
    )
    (net (code "92") (name "Net-(U3-B)") (class "Default")
      (node (ref "J1") (pin "4") (pinfunction "4_4") (pintype "passive"))
      (node (ref "U3") (pin "7") (pinfunction "B_7") (pintype "bidirectional"))
    )
    (net (code "93") (name "Net-(U3-Y)") (class "Default")
      (node (ref "J1") (pin "6") (pinfunction "6_6") (pintype "passive"))
      (node (ref "U3") (pin "5") (pinfunction "Y_5") (pintype "bidirectional"))
    )
    (net (code "94") (name "Net-(U3-Z)") (class "Default")
      (node (ref "J1") (pin "5") (pinfunction "5_5") (pintype "passive"))
      (node (ref "U3") (pin "6") (pinfunction "Z_6") (pintype "bidirectional"))
    )
    (net (code "95") (name "Net-(U4-A)") (class "Default")
      (node (ref "J2") (pin "3") (pinfunction "3_3") (pintype "passive"))
      (node (ref "U4") (pin "8") (pinfunction "A_8") (pintype "bidirectional"))
    )
    (net (code "96") (name "Net-(U4-B)") (class "Default")
      (node (ref "J2") (pin "4") (pinfunction "4_4") (pintype "passive"))
      (node (ref "U4") (pin "7") (pinfunction "B_7") (pintype "bidirectional"))
    )
    (net (code "97") (name "Net-(U4-Y)") (class "Default")
      (node (ref "J2") (pin "6") (pinfunction "6_6") (pintype "passive"))
      (node (ref "U4") (pin "5") (pinfunction "Y_5") (pintype "bidirectional"))
    )
    (net (code "98") (name "Net-(U4-Z)") (class "Default")
      (node (ref "J2") (pin "5") (pinfunction "5_5") (pintype "passive"))
      (node (ref "U4") (pin "6") (pinfunction "Z_6") (pintype "bidirectional"))
    )
    (net (code "99") (name "Net-(U5-A)") (class "Default")
      (node (ref "J3") (pin "3") (pinfunction "3_3") (pintype "passive"))
      (node (ref "U5") (pin "8") (pinfunction "A_8") (pintype "bidirectional"))
    )
    (net (code "100") (name "Net-(U5-B)") (class "Default")
      (node (ref "J3") (pin "4") (pinfunction "4_4") (pintype "passive"))
      (node (ref "U5") (pin "7") (pinfunction "B_7") (pintype "bidirectional"))
    )
    (net (code "101") (name "Net-(U5-Y)") (class "Default")
      (node (ref "J3") (pin "6") (pinfunction "6_6") (pintype "passive"))
      (node (ref "U5") (pin "5") (pinfunction "Y_5") (pintype "bidirectional"))
    )
    (net (code "102") (name "Net-(U5-Z)") (class "Default")
      (node (ref "J3") (pin "5") (pinfunction "5_5") (pintype "passive"))
      (node (ref "U5") (pin "6") (pinfunction "Z_6") (pintype "bidirectional"))
    )
    (net (code "103") (name "Net-(U6-A)") (class "Default")
      (node (ref "J4") (pin "3") (pinfunction "3_3") (pintype "passive"))
      (node (ref "U6") (pin "8") (pinfunction "A_8") (pintype "bidirectional"))
    )
    (net (code "104") (name "Net-(U6-B)") (class "Default")
      (node (ref "J4") (pin "4") (pinfunction "4_4") (pintype "passive"))
      (node (ref "U6") (pin "7") (pinfunction "B_7") (pintype "bidirectional"))
    )
    (net (code "105") (name "Net-(U6-Y)") (class "Default")
      (node (ref "J4") (pin "6") (pinfunction "6_6") (pintype "passive"))
      (node (ref "U6") (pin "5") (pinfunction "Y_5") (pintype "bidirectional"))
    )
    (net (code "106") (name "Net-(U6-Z)") (class "Default")
      (node (ref "J4") (pin "5") (pinfunction "5_5") (pintype "passive"))
      (node (ref "U6") (pin "6") (pinfunction "Z_6") (pintype "bidirectional"))
    )
    (net (code "107") (name "unconnected-(TP1-RTCK-Pad7)") (class "Default")
      (node (ref "TP1") (pin "7") (pinfunction "RTCK_7") (pintype "bidirectional"))
    )
    (net (code "108") (name "unconnected-(U2-JTAGSEL-Pad73)") (class "Default")
      (node (ref "U2") (pin "73") (pinfunction "JTAGSEL_73") (pintype "bidirectional"))
    )
    (net (code "109") (name "unconnected-(U2-PA2-Pad66)") (class "Default")
      (node (ref "U2") (pin "66") (pinfunction "PA2_66") (pintype "bidirectional"))
    )
    (net (code "110") (name "unconnected-(U2-PA3{slash}TWD0-Pad64)") (class "Default")
      (node (ref "U2") (pin "64") (pinfunction "PA3/TWD0_64") (pintype "bidirectional"))
    )
    (net (code "111") (name "unconnected-(U2-PA7{slash}XIN32-Pad24)") (class "Default")
      (node (ref "U2") (pin "24") (pinfunction "PA7/XIN32_24") (pintype "bidirectional"))
    )
    (net (code "112") (name "unconnected-(U2-PA12{slash}PWMC0_PWMH1-Pad48)") (class "Default")
      (node (ref "U2") (pin "48") (pinfunction "PA12/PWMC0_PWMH1_48") (pintype "bidirectional"))
    )
    (net (code "113") (name "unconnected-(U2-PA14{slash}WMC0_PWMH3-Pad34)") (class "Default")
      (node (ref "U2") (pin "34") (pinfunction "PA14/WMC0_PWMH3_34") (pintype "bidirectional"))
    )
    (net (code "114") (name "unconnected-(U2-PA24-Pad38)") (class "Default")
      (node (ref "U2") (pin "38") (pinfunction "PA24_38") (pintype "bidirectional"))
    )
    (net (code "115") (name "unconnected-(U2-PA25-Pad40)") (class "Default")
      (node (ref "U2") (pin "40") (pinfunction "PA25_40") (pintype "bidirectional"))
    )
    (net (code "116") (name "unconnected-(U2-PA26-Pad42)") (class "Default")
      (node (ref "U2") (pin "42") (pinfunction "PA26_42") (pintype "bidirectional"))
    )
    (net (code "117") (name "unconnected-(U2-PB12{slash}ERASE-Pad61)") (class "Default")
      (node (ref "U2") (pin "61") (pinfunction "PB12/ERASE_61") (pintype "bidirectional"))
    )
    (net (code "118") (name "unconnected-(U2-PD16-Pad56)") (class "Default")
      (node (ref "U2") (pin "56") (pinfunction "PD16_56") (pintype "bidirectional"))
    )
    (net (code "119") (name "unconnected-(U2-PD17-Pad53)") (class "Default")
      (node (ref "U2") (pin "53") (pinfunction "PD17_53") (pintype "bidirectional"))
    )
    (net (code "120") (name "unconnected-(U2-PD24-Pad37)") (class "Default")
      (node (ref "U2") (pin "37") (pinfunction "PD24_37") (pintype "bidirectional"))
    )
    (net (code "121") (name "unconnected-(U2-PD31-Pad2)") (class "Default")
      (node (ref "U2") (pin "2") (pinfunction "PD31_2") (pintype "bidirectional"))
    )
    (net (code "122") (name "unconnected-(U2-TST-Pad60)") (class "Default")
      (node (ref "U2") (pin "60") (pinfunction "TST_60") (pintype "bidirectional"))
    )
  )
)
